# Power.net
KiCad netlist of a schematic drawn in Altium Designer
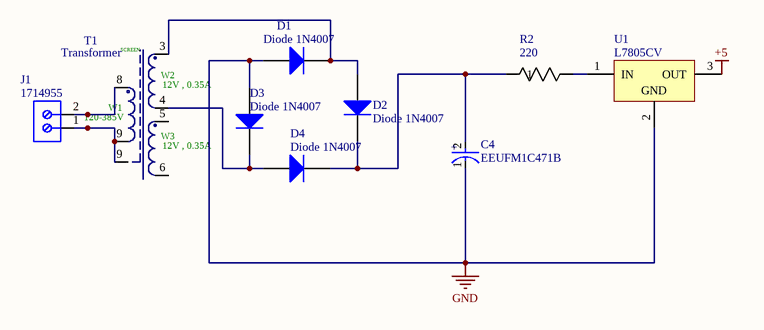
[diagram p0: Power.SchDoc]

(export (version "E")
  (design (tool "Eeschema 10.0.6"))
  (components
    (comp (ref "C4")
      (value "EEUFM1C471B")
      (footprint "FP-RAD-TH-D_10_0_5-L_12_5-MFG")
      (description "Aluminum Electrolytic Capacitors (Radial Lead Type) 470uF ±20% 16V")
      (fields (field (name "TOLERANCE") "20%"))
      (libsource (lib "Altium Content Vault") (part "203bc49f2ac43e59fd269a8c329ed05"))
    )
    (comp (ref "D1")
      (value "Diode 1N4007")
      (footprint "DO-41")
      (description "1 Amp General Purpose Rectifier")
      (fields (field (name "PUBLISHER") "Altium Limited"))
      (libsource (lib "Miscellaneous Devices") (part "Diode 1N4007"))
    )
    (comp (ref "D2")
      (value "Diode 1N4007")
      (footprint "DO-41")
      (description "1 Amp General Purpose Rectifier")
      (fields (field (name "PUBLISHER") "Altium Limited"))
      (libsource (lib "Miscellaneous Devices") (part "Diode 1N4007"))
    )
    (comp (ref "D3")
      (value "Diode 1N4007")
      (footprint "DO-41")
      (description "1 Amp General Purpose Rectifier")
      (fields (field (name "PUBLISHER") "Altium Limited"))
      (libsource (lib "Miscellaneous Devices") (part "Diode 1N4007"))
    )
    (comp (ref "D4")
      (value "Diode 1N4007")
      (footprint "DO-41")
      (description "1 Amp General Purpose Rectifier")
      (fields (field (name "PUBLISHER") "Altium Limited"))
      (libsource (lib "Miscellaneous Devices") (part "Diode 1N4007"))
    )
    (comp (ref "J1")
      (value "1714955")
      (footprint "PHOE-1714955_V")
      (description "PC Terminal Block, Pitch 6.35 mm, 1 x 2 Position, Height 21.5 mm, Tail Lenght 5.1 mm, RoHS, Bulk")
      (fields (field (name "MANUFACTURER") "Phoenix Contact"))
      (libsource (lib "Altium Content Vault") (part "CN-1P-F-TB2"))
    )
    (comp (ref "R2")
      (value "220")
      (footprint "RES_AC01_VIS")
      (description "AC01000006809JA100 Resistor, 68 Ohm, ± 5%, 1 W, Axial Leaded, Wirewound, General Purpose")
      (fields (field (name "TOLERANCE") "5%"))
      (libsource (lib "Altium Content Vault") (part "AC01000006809JA100"))
    )
    (comp (ref "T1")
      (value "Transformer")
      (footprint "EE16_7_4 (E16)")
      (description "Off-Line Transformer WE-UNIT , L=0.9mH")
      (fields (field (name "MANUFACTURER") "Wuerth Elektronik") (field (name "PARTNUMBER") "7491182012"))
      (libsource (lib "Altium Content Vault") (part "WE-7491182012"))
    )
    (comp (ref "U1")
      (value "L7805CV")
      (footprint "TO220")
      (description "Positive Voltage Regulator, 5V, 3-Pin TO-220")
      (libsource (lib "Altium Content Vault") (part "PM-REG-L4940-SIL3"))
    )
  )
  (nets
    (net (code "1") (name "+5") (class "Default")
      (node (ref "U1") (pin "3") (pinfunction "OUT_3") (pintype "power_in"))
    )
    (net (code "2") (name "GND") (class "Default")
      (node (ref "C4") (pin "1") (pinfunction "C_1") (pintype "passive"))
      (node (ref "D1") (pin "1") (pinfunction "A_1") (pintype "passive"))
      (node (ref "D3") (pin "1") (pinfunction "A_1") (pintype "passive"))
      (node (ref "U1") (pin "2") (pinfunction "GND_2") (pintype "power_in"))
    )
    (net (code "3") (name "Net-(C4-A)") (class "Default")
      (node (ref "C4") (pin "2") (pinfunction "A_2") (pintype "passive"))
      (node (ref "D2") (pin "2") (pinfunction "K_2") (pintype "passive"))
      (node (ref "D4") (pin "2") (pinfunction "K_2") (pintype "passive"))
      (node (ref "R2") (pin "1") (pinfunction "1_1") (pintype "passive"))
    )
    (net (code "4") (name "Net-(D1-K)") (class "Default")
      (node (ref "D1") (pin "2") (pinfunction "K_2") (pintype "passive"))
      (node (ref "D2") (pin "1") (pinfunction "A_1") (pintype "passive"))
      (node (ref "T1") (pin "3") (pinfunction "3_3") (pintype "passive"))
    )
    (net (code "5") (name "Net-(D3-K)") (class "Default")
      (node (ref "D3") (pin "2") (pinfunction "K_2") (pintype "passive"))
      (node (ref "D4") (pin "1") (pinfunction "A_1") (pintype "passive"))
      (node (ref "T1") (pin "4") (pinfunction "4_4") (pintype "passive"))
    )
    (net (code "6") (name "Net-(J1-Pad1)") (class "Default")
      (node (ref "J1") (pin "1") (pinfunction "1_1") (pintype "passive"))
      (node (ref "T1") (pin "9") (pinfunction "9_9") (pintype "passive"))
    )
    (net (code "7") (name "Net-(J1-Pad2)") (class "Default")
      (node (ref "J1") (pin "2") (pinfunction "2_2") (pintype "passive"))
      (node (ref "T1") (pin "8") (pinfunction "8_8") (pintype "passive"))
    )
    (net (code "8") (name "Net-(U1-IN)") (class "Default")
      (node (ref "R2") (pin "2") (pinfunction "2_2") (pintype "passive"))
      (node (ref "U1") (pin "1") (pinfunction "IN_1") (pintype "power_in"))
    )
    (net (code "9") (name "unconnected-(T1-Pad5)") (class "Default")
      (node (ref "T1") (pin "5") (pinfunction "5_5") (pintype "passive"))
    )
    (net (code "10") (name "unconnected-(T1-Pad6)") (class "Default")
      (node (ref "T1") (pin "6") (pinfunction "6_6") (pintype "passive"))
    )
  )
)
